# Camera.net
KiCad netlist of a schematic drawn in EAGLE
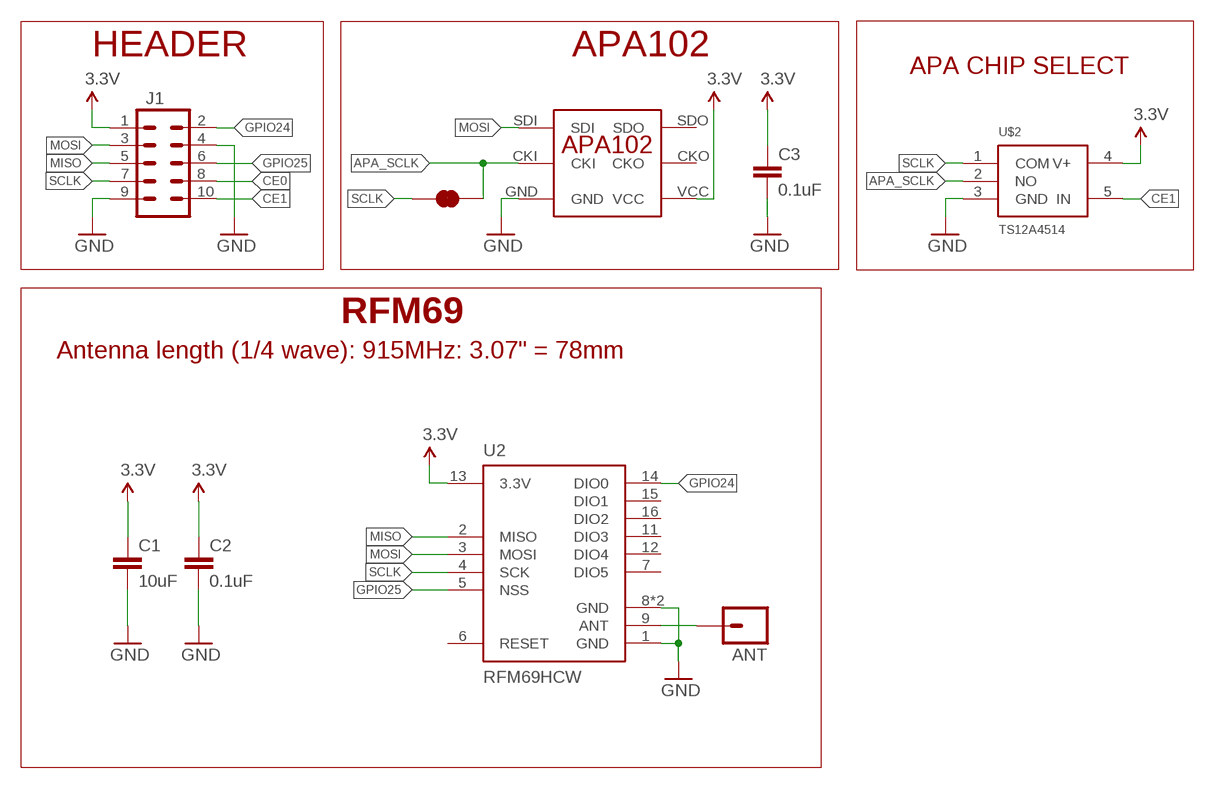
[diagram p0: schematic, sheet 1]

(export (version "E")
  (design (tool "Eeschema 10.0.6"))
  (components
    (comp (ref "ANT")
      (value "M01PTH_NO_SILK_YES_STOP")
      (footprint "eagle-import:1X01_NO_SILK")
      (libsource (lib "eagle-import") (part "M01PTH_NO_SILK_YES_STOP"))
    )
    (comp (ref "C1")
      (value "10uF")
      (footprint "eagle-import:1210")
      (libsource (lib "eagle-import") (part "10UF50V20%(1210)"))
    )
    (comp (ref "C2")
      (value "0.1uF")
      (footprint "eagle-import:0603-CAP@1")
      (libsource (lib "eagle-import") (part "0.1UF-25V(+80/-20%)(0603)"))
    )
    (comp (ref "C3")
      (value "0.1uF")
      (footprint "eagle-import:0603-CAP@1")
      (libsource (lib "eagle-import") (part "0.1UF-25V(+80/-20%)(0603)"))
    )
    (comp (ref "J1")
      (value "M05X2NO_SILK")
      (footprint "eagle-import:2X5_NOSILK")
      (libsource (lib "eagle-import") (part "M05X2NO_SILK"))
    )
    (comp (ref "JP1")
      (value "JUMPER-PAD-2-NC_BY_TRACE")
      (footprint "eagle-import:PAD-JUMPER-2-NC_BY_TRACE_YES_SILK")
      (libsource (lib "eagle-import") (part "JUMPER-PAD-2-NC_BY_TRACE"))
    )
    (comp (ref "U$1")
      (value "APA102")
      (footprint "eagle-import:APA102")
      (libsource (lib "eagle-import") (part "APA102"))
    )
    (comp (ref "U$2")
      (value "TS12A4514")
      (footprint "eagle-import:SOT-23")
      (libsource (lib "eagle-import") (part "TS12A4514"))
    )
    (comp (ref "U2")
      (value "RFM69HCW")
      (footprint "eagle-import:RFM69HCW-XXXS2")
      (libsource (lib "eagle-import") (part "RFM69HCW"))
    )
  )
  (nets
    (net (code "1") (name "3.3V") (class "Default")
      (node (ref "C1") (pin "1") (pinfunction "1_1") (pintype "passive"))
      (node (ref "C2") (pin "1") (pinfunction "1_1") (pintype "passive"))
      (node (ref "C3") (pin "1") (pinfunction "1_1") (pintype "passive"))
      (node (ref "J1") (pin "1") (pinfunction "1_1") (pintype "passive"))
      (node (ref "U$1") (pin "VCC") (pinfunction "VCC_VCC") (pintype "bidirectional"))
      (node (ref "U$2") (pin "4") (pinfunction "V+_4") (pintype "bidirectional"))
      (node (ref "U2") (pin "13") (pinfunction "3.3V_13") (pintype "power_in"))
    )
    (net (code "2") (name "APA_SCLK") (class "Default")
      (node (ref "JP1") (pin "2") (pinfunction "2_2") (pintype "passive"))
      (node (ref "U$1") (pin "CKI") (pinfunction "CKI_CKI") (pintype "bidirectional"))
      (node (ref "U$2") (pin "2") (pinfunction "NO_2") (pintype "bidirectional"))
    )
    (net (code "3") (name "CE0") (class "Default")
      (node (ref "J1") (pin "8") (pinfunction "8_8") (pintype "passive"))
    )
    (net (code "4") (name "CE1") (class "Default")
      (node (ref "J1") (pin "10") (pinfunction "10_10") (pintype "passive"))
      (node (ref "U$2") (pin "5") (pinfunction "IN_5") (pintype "bidirectional"))
    )
    (net (code "5") (name "GND") (class "Default")
      (node (ref "C1") (pin "2") (pinfunction "2_2") (pintype "passive"))
      (node (ref "C2") (pin "2") (pinfunction "2_2") (pintype "passive"))
      (node (ref "C3") (pin "2") (pinfunction "2_2") (pintype "passive"))
      (node (ref "J1") (pin "4") (pinfunction "4_4") (pintype "passive"))
      (node (ref "J1") (pin "9") (pinfunction "9_9") (pintype "passive"))
      (node (ref "U$1") (pin "GND") (pinfunction "GND_GND") (pintype "bidirectional"))
      (node (ref "U$2") (pin "3") (pinfunction "GND_3") (pintype "bidirectional"))
      (node (ref "U2") (pin "1") (pinfunction "GND_1") (pintype "power_in"))
      (node (ref "U2") (pin "10") (pinfunction "GND_10") (pintype "power_in"))
      (node (ref "U2") (pin "8") (pinfunction "GND_8") (pintype "power_in"))
    )
    (net (code "6") (name "GPIO24") (class "Default")
      (node (ref "J1") (pin "2") (pinfunction "2_2") (pintype "passive"))
      (node (ref "U2") (pin "14") (pinfunction "DIO0_14") (pintype "bidirectional"))
    )
    (net (code "7") (name "GPIO25") (class "Default")
      (node (ref "J1") (pin "6") (pinfunction "6_6") (pintype "passive"))
      (node (ref "U2") (pin "5") (pinfunction "NSS_5") (pintype "input"))
    )
    (net (code "8") (name "MISO") (class "Default")
      (node (ref "J1") (pin "5") (pinfunction "5_5") (pintype "passive"))
      (node (ref "U2") (pin "2") (pinfunction "MISO_2") (pintype "bidirectional"))
    )
    (net (code "9") (name "MOSI") (class "Default")
      (node (ref "J1") (pin "3") (pinfunction "3_3") (pintype "passive"))
      (node (ref "U$1") (pin "SDI") (pinfunction "SDI_SDI") (pintype "bidirectional"))
      (node (ref "U2") (pin "3") (pinfunction "MOSI_3") (pintype "input"))
    )
    (net (code "10") (name "Net-(U2-ANT)") (class "Default")
      (node (ref "ANT") (pin "1") (pinfunction "1_1") (pintype "passive"))
      (node (ref "U2") (pin "9") (pinfunction "ANT_9") (pintype "passive"))
    )
    (net (code "11") (name "SCLK") (class "Default")
      (node (ref "J1") (pin "7") (pinfunction "7_7") (pintype "passive"))
      (node (ref "JP1") (pin "1") (pinfunction "1_1") (pintype "passive"))
      (node (ref "U$2") (pin "1") (pinfunction "COM_1") (pintype "bidirectional"))
      (node (ref "U2") (pin "4") (pinfunction "SCK_4") (pintype "input"))
    )
    (net (code "12") (name "unconnected-(U$1-PadCKO)") (class "Default")
      (node (ref "U$1") (pin "CKO") (pinfunction "CKO_CKO") (pintype "bidirectional"))
    )
    (net (code "13") (name "unconnected-(U$1-PadSDO)") (class "Default")
      (node (ref "U$1") (pin "SDO") (pinfunction "SDO_SDO") (pintype "bidirectional"))
    )
    (net (code "14") (name "unconnected-(U2-DIO1-Pad15)") (class "Default")
      (node (ref "U2") (pin "15") (pinfunction "DIO1_15") (pintype "bidirectional"))
    )
    (net (code "15") (name "unconnected-(U2-DIO2-Pad16)") (class "Default")
      (node (ref "U2") (pin "16") (pinfunction "DIO2_16") (pintype "bidirectional"))
    )
    (net (code "16") (name "unconnected-(U2-DIO3-Pad11)") (class "Default")
      (node (ref "U2") (pin "11") (pinfunction "DIO3_11") (pintype "bidirectional"))
    )
    (net (code "17") (name "unconnected-(U2-DIO4-Pad12)") (class "Default")
      (node (ref "U2") (pin "12") (pinfunction "DIO4_12") (pintype "bidirectional"))
    )
    (net (code "18") (name "unconnected-(U2-DIO5-Pad7)") (class "Default")
      (node (ref "U2") (pin "7") (pinfunction "DIO5_7") (pintype "bidirectional"))
    )
    (net (code "19") (name "unconnected-(U2-RESET-Pad6)") (class "Default")
      (node (ref "U2") (pin "6") (pinfunction "RESET_6") (pintype "input"))
    )
  )
)
